# Vertex_V1.net
KiCad netlist of a schematic drawn in EAGLE
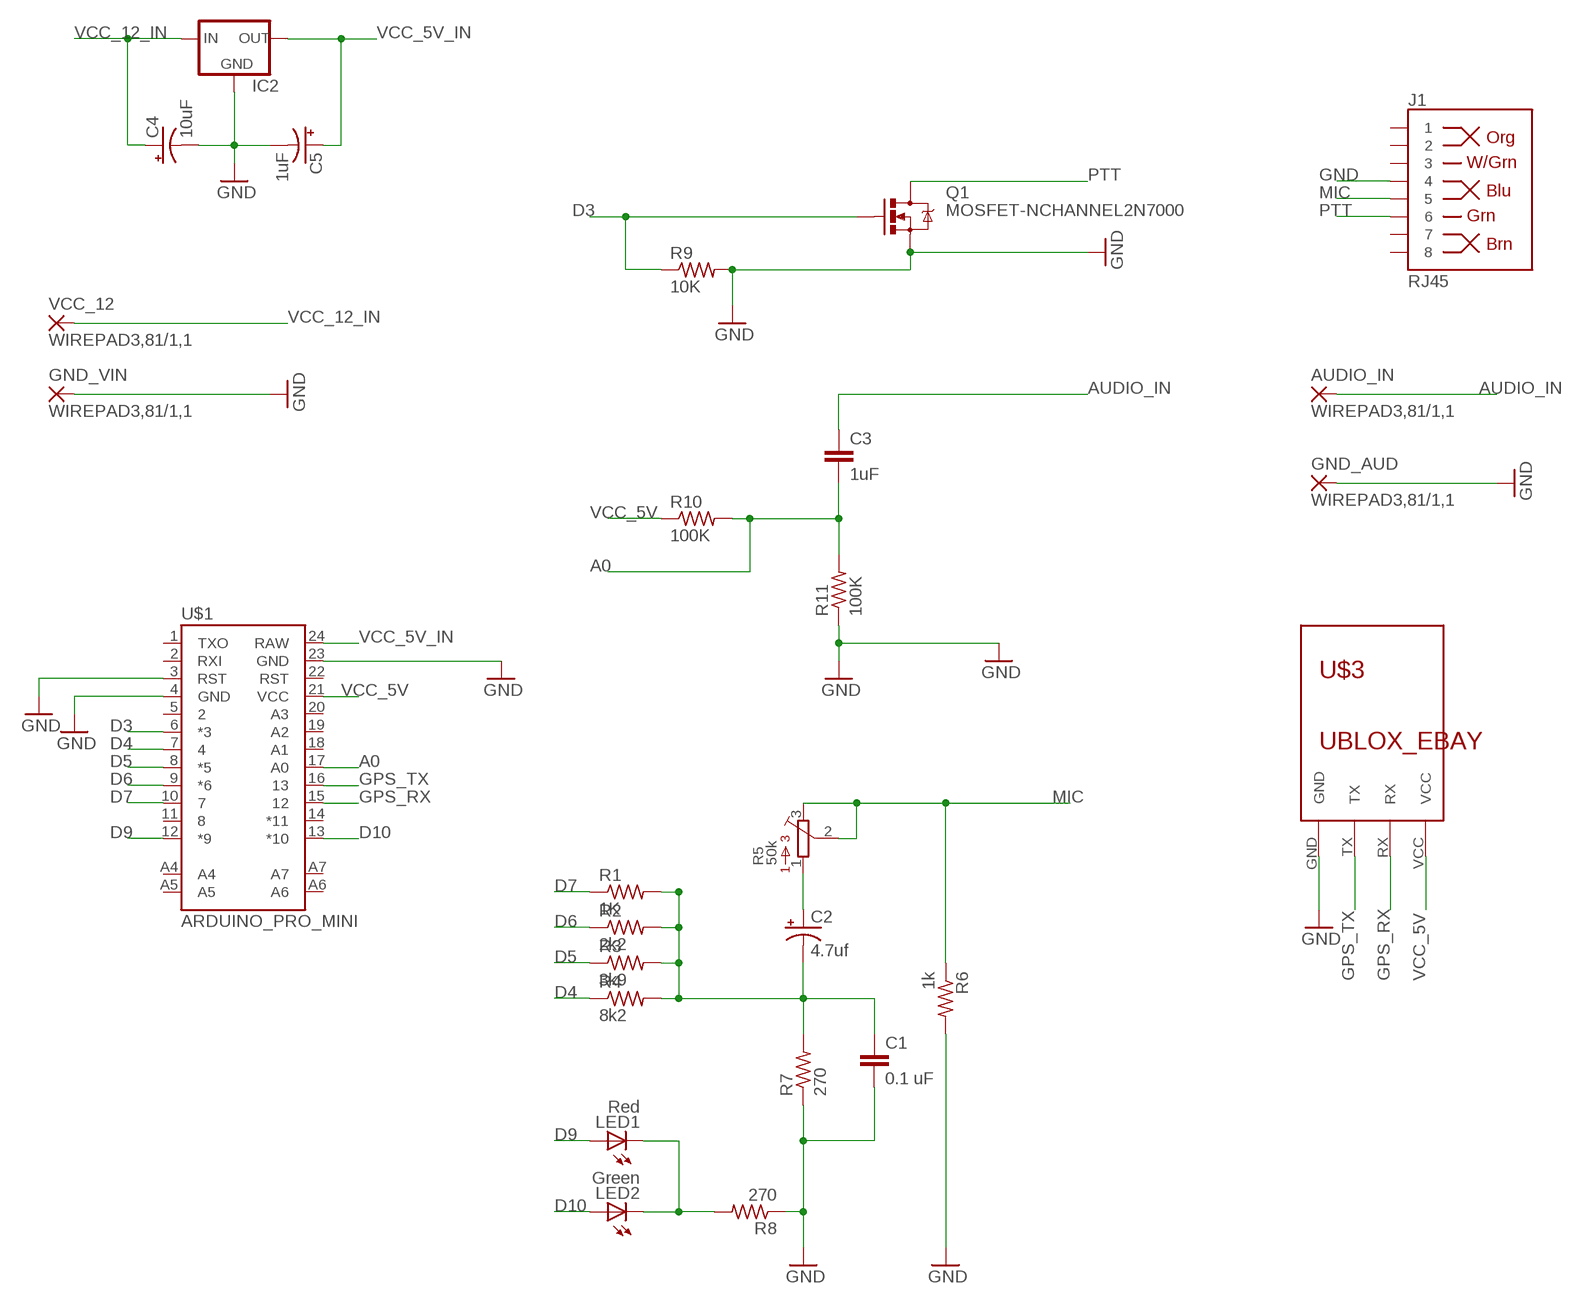
[diagram p0: schematic, sheet 1]

(export (version "E")
  (design (tool "Eeschema 10.0.6"))
  (components
    (comp (ref "AUDIO_IN")
      (value "WIREPAD3,81/1,1")
      (footprint "eagle-import:3,81_1,1")
      (libsource (lib "eagle-import") (part "WIREPAD3,81/1,1"))
    )
    (comp (ref "C1")
      (value "0.1 uF")
      (footprint "eagle-import:CAP-PTH-SMALL-KIT")
      (libsource (lib "eagle-import") (part "0.1UF-50V-20%(PTH)KIT-EZ"))
    )
    (comp (ref "C2")
      (value "4.7uf")
      (footprint "eagle-import:CPOL-RADIAL-10UF-25V")
      (libsource (lib "eagle-import") (part "CAP_POLPTH2"))
    )
    (comp (ref "C3")
      (value "1uF")
      (footprint "eagle-import:CAP-PTH-SMALL-KIT")
      (libsource (lib "eagle-import") (part "0.1UF-50V-20%(PTH)KIT-EZ"))
    )
    (comp (ref "C4")
      (value "10uF")
      (footprint "eagle-import:CPOL-RADIAL-10UF-25V")
      (libsource (lib "eagle-import") (part "CAP_POLPTH2"))
    )
    (comp (ref "C5")
      (value "1uF")
      (footprint "eagle-import:CPOL-RADIAL-10UF-25V")
      (libsource (lib "eagle-import") (part "CAP_POLPTH2"))
    )
    (comp (ref "GND_AUD")
      (value "WIREPAD3,81/1,1")
      (footprint "eagle-import:3,81_1,1")
      (libsource (lib "eagle-import") (part "WIREPAD3,81/1,1"))
    )
    (comp (ref "GND_VIN")
      (value "WIREPAD3,81/1,1")
      (footprint "eagle-import:3,81_1,1")
      (libsource (lib "eagle-import") (part "WIREPAD3,81/1,1"))
    )
    (comp (ref "IC2")
      (value "78XXS")
      (footprint "eagle-import:78XXS")
      (libsource (lib "eagle-import") (part "78XXS"))
    )
    (comp (ref "J1")
      (value "RJ45")
      (footprint "eagle-import:RJ45-8")
      (libsource (lib "eagle-import") (part "RJ45-8PTH"))
    )
    (comp (ref "LED1")
      (value "Red")
      (footprint "eagle-import:LED5MM")
      (libsource (lib "eagle-import") (part "LED5MM"))
    )
    (comp (ref "LED2")
      (value "Green")
      (footprint "eagle-import:LED5MM")
      (libsource (lib "eagle-import") (part "LED5MM"))
    )
    (comp (ref "Q1")
      (value "MOSFET-NCHANNEL2N7000")
      (footprint "eagle-import:TO-92")
      (libsource (lib "eagle-import") (part "MOSFET-NCHANNEL2N7000"))
    )
    (comp (ref "R1")
      (value "1K")
      (footprint "eagle-import:0309V")
      (libsource (lib "eagle-import") (part "R-US_0309/V"))
    )
    (comp (ref "R2")
      (value "2k2")
      (footprint "eagle-import:0309V")
      (libsource (lib "eagle-import") (part "R-US_0309/V"))
    )
    (comp (ref "R3")
      (value "3k9")
      (footprint "eagle-import:0309V")
      (libsource (lib "eagle-import") (part "R-US_0309/V"))
    )
    (comp (ref "R4")
      (value "8k2")
      (footprint "eagle-import:0309V")
      (libsource (lib "eagle-import") (part "R-US_0309/V"))
    )
    (comp (ref "R5")
      (value "50k")
      (footprint "eagle-import:3362P")
      (libsource (lib "eagle-import") (part "3362P"))
    )
    (comp (ref "R6")
      (value "1k")
      (footprint "eagle-import:0309V")
      (libsource (lib "eagle-import") (part "R-US_0309/V"))
    )
    (comp (ref "R7")
      (value "270")
      (footprint "eagle-import:0309V")
      (libsource (lib "eagle-import") (part "R-US_0309/V"))
    )
    (comp (ref "R8")
      (value "270")
      (footprint "eagle-import:0309V")
      (libsource (lib "eagle-import") (part "R-US_0309/V"))
    )
    (comp (ref "R9")
      (value "10K")
      (footprint "eagle-import:0309V")
      (libsource (lib "eagle-import") (part "R-US_0309/V"))
    )
    (comp (ref "R10")
      (value "100K")
      (footprint "eagle-import:0309V")
      (libsource (lib "eagle-import") (part "R-US_0309/V"))
    )
    (comp (ref "R11")
      (value "100K")
      (footprint "eagle-import:0309V")
      (libsource (lib "eagle-import") (part "R-US_0309/V"))
    )
    (comp (ref "U$1")
      (value "ARDUINO_PRO_MINI")
      (footprint "eagle-import:ARDUINO_PRO_MINI")
      (libsource (lib "eagle-import") (part "ARDUINO_PRO_MINI"))
    )
    (comp (ref "U$3")
      (value "UBLOX_EBAY")
      (footprint "eagle-import:UBLOX_EBAY")
      (libsource (lib "eagle-import") (part "UBLOX_EBAY"))
    )
    (comp (ref "VCC_12")
      (value "WIREPAD3,81/1,1")
      (footprint "eagle-import:3,81_1,1")
      (libsource (lib "eagle-import") (part "WIREPAD3,81/1,1"))
    )
  )
  (nets
    (net (code "1") (name "/A0") (class "Default")
      (node (ref "C3") (pin "2") (pinfunction "2_2") (pintype "passive"))
      (node (ref "R10") (pin "2") (pinfunction "2_2") (pintype "passive"))
      (node (ref "R11") (pin "2") (pinfunction "2_2") (pintype "passive"))
      (node (ref "U$1") (pin "17") (pinfunction "A0_17") (pintype "bidirectional"))
    )
    (net (code "2") (name "/AUDIO_IN") (class "Default")
      (node (ref "AUDIO_IN") (pin "1") (pinfunction "P_1") (pintype "passive"))
      (node (ref "C3") (pin "1") (pinfunction "1_1") (pintype "passive"))
    )
    (net (code "3") (name "/D3") (class "Default")
      (node (ref "Q1") (pin "2") (pinfunction "G_2") (pintype "passive"))
      (node (ref "R9") (pin "1") (pinfunction "1_1") (pintype "passive"))
      (node (ref "U$1") (pin "6") (pinfunction "*3_6") (pintype "bidirectional"))
    )
    (net (code "4") (name "/D4") (class "Default")
      (node (ref "R4") (pin "1") (pinfunction "1_1") (pintype "passive"))
      (node (ref "U$1") (pin "7") (pinfunction "4_7") (pintype "bidirectional"))
    )
    (net (code "5") (name "/D5") (class "Default")
      (node (ref "R3") (pin "1") (pinfunction "1_1") (pintype "passive"))
      (node (ref "U$1") (pin "8") (pinfunction "*5_8") (pintype "bidirectional"))
    )
    (net (code "6") (name "/D6") (class "Default")
      (node (ref "R2") (pin "1") (pinfunction "1_1") (pintype "passive"))
      (node (ref "U$1") (pin "9") (pinfunction "*6_9") (pintype "bidirectional"))
    )
    (net (code "7") (name "/D7") (class "Default")
      (node (ref "R1") (pin "1") (pinfunction "1_1") (pintype "passive"))
      (node (ref "U$1") (pin "10") (pinfunction "7_10") (pintype "bidirectional"))
    )
    (net (code "8") (name "/D9") (class "Default")
      (node (ref "LED1") (pin "A") (pinfunction "A_A") (pintype "passive"))
      (node (ref "U$1") (pin "12") (pinfunction "*9_12") (pintype "bidirectional"))
    )
    (net (code "9") (name "/D10") (class "Default")
      (node (ref "LED2") (pin "A") (pinfunction "A_A") (pintype "passive"))
      (node (ref "U$1") (pin "13") (pinfunction "*10_13") (pintype "bidirectional"))
    )
    (net (code "10") (name "/GPS_RX") (class "Default")
      (node (ref "U$1") (pin "15") (pinfunction "12_15") (pintype "bidirectional"))
      (node (ref "U$3") (pin "RX") (pinfunction "RX_RX") (pintype "bidirectional"))
    )
    (net (code "11") (name "/GPS_TX") (class "Default")
      (node (ref "U$1") (pin "16") (pinfunction "13_16") (pintype "bidirectional"))
      (node (ref "U$3") (pin "TX") (pinfunction "TX_TX") (pintype "bidirectional"))
    )
    (net (code "12") (name "/MIC") (class "Default")
      (node (ref "J1") (pin "5") (pinfunction "5_5") (pintype "bidirectional"))
      (node (ref "R5") (pin "2") (pinfunction "2_2") (pintype "passive"))
      (node (ref "R5") (pin "3") (pinfunction "3_3") (pintype "passive"))
      (node (ref "R6") (pin "1") (pinfunction "1_1") (pintype "passive"))
    )
    (net (code "13") (name "/PTT") (class "Default")
      (node (ref "J1") (pin "6") (pinfunction "6_6") (pintype "bidirectional"))
      (node (ref "Q1") (pin "3") (pinfunction "D_3") (pintype "passive"))
    )
    (net (code "14") (name "/VCC_5V") (class "Default")
      (node (ref "R10") (pin "1") (pinfunction "1_1") (pintype "passive"))
      (node (ref "U$1") (pin "21") (pinfunction "VCC_21") (pintype "bidirectional"))
      (node (ref "U$3") (pin "VCC") (pinfunction "VCC_VCC") (pintype "bidirectional"))
    )
    (net (code "15") (name "/VCC_5V_IN") (class "Default")
      (node (ref "C5") (pin "1") (pinfunction "+_1") (pintype "passive"))
      (node (ref "IC2") (pin "OUT") (pinfunction "OUT_OUT") (pintype "passive"))
      (node (ref "U$1") (pin "24") (pinfunction "RAW_24") (pintype "bidirectional"))
    )
    (net (code "16") (name "/VCC_12_IN") (class "Default")
      (node (ref "C4") (pin "1") (pinfunction "+_1") (pintype "passive"))
      (node (ref "IC2") (pin "IN") (pinfunction "IN_IN") (pintype "input"))
      (node (ref "VCC_12") (pin "1") (pinfunction "P_1") (pintype "passive"))
    )
    (net (code "17") (name "GND") (class "Default")
      (node (ref "C1") (pin "2") (pinfunction "2_2") (pintype "passive"))
      (node (ref "C4") (pin "2") (pinfunction "-_2") (pintype "passive"))
      (node (ref "C5") (pin "2") (pinfunction "-_2") (pintype "passive"))
      (node (ref "GND_AUD") (pin "1") (pinfunction "P_1") (pintype "passive"))
      (node (ref "GND_VIN") (pin "1") (pinfunction "P_1") (pintype "passive"))
      (node (ref "IC2") (pin "GND") (pinfunction "GND_GND") (pintype "input"))
      (node (ref "J1") (pin "4") (pinfunction "4_4") (pintype "bidirectional"))
      (node (ref "Q1") (pin "1") (pinfunction "S_1") (pintype "passive"))
      (node (ref "R11") (pin "1") (pinfunction "1_1") (pintype "passive"))
      (node (ref "R6") (pin "2") (pinfunction "2_2") (pintype "passive"))
      (node (ref "R7") (pin "1") (pinfunction "1_1") (pintype "passive"))
      (node (ref "R8") (pin "1") (pinfunction "1_1") (pintype "passive"))
      (node (ref "R9") (pin "2") (pinfunction "2_2") (pintype "passive"))
      (node (ref "U$1") (pin "23") (pinfunction "GND_23") (pintype "bidirectional"))
      (node (ref "U$1") (pin "3") (pinfunction "RST_3") (pintype "bidirectional"))
      (node (ref "U$1") (pin "4") (pinfunction "GND_4") (pintype "bidirectional"))
      (node (ref "U$3") (pin "GND") (pinfunction "GND_GND") (pintype "bidirectional"))
    )
    (net (code "18") (name "Net-(C2-+)") (class "Default")
      (node (ref "C2") (pin "1") (pinfunction "+_1") (pintype "passive"))
      (node (ref "R5") (pin "1") (pinfunction "1_1") (pintype "passive"))
    )
    (net (code "19") (name "Net-(C2--)") (class "Default")
      (node (ref "C1") (pin "1") (pinfunction "1_1") (pintype "passive"))
      (node (ref "C2") (pin "2") (pinfunction "-_2") (pintype "passive"))
      (node (ref "R1") (pin "2") (pinfunction "2_2") (pintype "passive"))
      (node (ref "R2") (pin "2") (pinfunction "2_2") (pintype "passive"))
      (node (ref "R3") (pin "2") (pinfunction "2_2") (pintype "passive"))
      (node (ref "R4") (pin "2") (pinfunction "2_2") (pintype "passive"))
      (node (ref "R7") (pin "2") (pinfunction "2_2") (pintype "passive"))
    )
    (net (code "20") (name "Net-(LED1-C)") (class "Default")
      (node (ref "LED1") (pin "K") (pinfunction "C_K") (pintype "passive"))
      (node (ref "LED2") (pin "K") (pinfunction "C_K") (pintype "passive"))
      (node (ref "R8") (pin "2") (pinfunction "2_2") (pintype "passive"))
    )
    (net (code "21") (name "unconnected-(J1-Pad1)") (class "Default")
      (node (ref "J1") (pin "1") (pinfunction "1_1") (pintype "bidirectional"))
    )
    (net (code "22") (name "unconnected-(J1-Pad2)") (class "Default")
      (node (ref "J1") (pin "2") (pinfunction "2_2") (pintype "bidirectional"))
    )
    (net (code "23") (name "unconnected-(J1-Pad3)") (class "Default")
      (node (ref "J1") (pin "3") (pinfunction "3_3") (pintype "bidirectional"))
    )
    (net (code "24") (name "unconnected-(J1-Pad7)") (class "Default")
      (node (ref "J1") (pin "7") (pinfunction "7_7") (pintype "bidirectional"))
    )
    (net (code "25") (name "unconnected-(J1-Pad8)") (class "Default")
      (node (ref "J1") (pin "8") (pinfunction "8_8") (pintype "bidirectional"))
    )
    (net (code "26") (name "unconnected-(U$1-*11-Pad14)") (class "Default")
      (node (ref "U$1") (pin "14") (pinfunction "*11_14") (pintype "bidirectional"))
    )
    (net (code "27") (name "unconnected-(U$1-2-Pad5)") (class "Default")
      (node (ref "U$1") (pin "5") (pinfunction "2_5") (pintype "bidirectional"))
    )
    (net (code "28") (name "unconnected-(U$1-8-Pad11)") (class "Default")
      (node (ref "U$1") (pin "11") (pinfunction "8_11") (pintype "bidirectional"))
    )
    (net (code "29") (name "unconnected-(U$1-A1-Pad18)") (class "Default")
      (node (ref "U$1") (pin "18") (pinfunction "A1_18") (pintype "bidirectional"))
    )
    (net (code "30") (name "unconnected-(U$1-A2-Pad19)") (class "Default")
      (node (ref "U$1") (pin "19") (pinfunction "A2_19") (pintype "bidirectional"))
    )
    (net (code "31") (name "unconnected-(U$1-A3-Pad20)") (class "Default")
      (node (ref "U$1") (pin "20") (pinfunction "A3_20") (pintype "bidirectional"))
    )
    (net (code "32") (name "unconnected-(U$1-PadA4)") (class "Default")
      (node (ref "U$1") (pin "A4") (pinfunction "A4_A4") (pintype "bidirectional"))
    )
    (net (code "33") (name "unconnected-(U$1-PadA5)") (class "Default")
      (node (ref "U$1") (pin "A5") (pinfunction "A5_A5") (pintype "bidirectional"))
    )
    (net (code "34") (name "unconnected-(U$1-PadA6)") (class "Default")
      (node (ref "U$1") (pin "A6") (pinfunction "A6_A6") (pintype "bidirectional"))
    )
    (net (code "35") (name "unconnected-(U$1-PadA7)") (class "Default")
      (node (ref "U$1") (pin "A7") (pinfunction "A7_A7") (pintype "bidirectional"))
    )
    (net (code "36") (name "unconnected-(U$1-RST-Pad22)") (class "Default")
      (node (ref "U$1") (pin "22") (pinfunction "RST_22") (pintype "bidirectional"))
    )
    (net (code "37") (name "unconnected-(U$1-RXI-Pad2)") (class "Default")
      (node (ref "U$1") (pin "2") (pinfunction "RXI_2") (pintype "bidirectional"))
    )
    (net (code "38") (name "unconnected-(U$1-TXO-Pad1)") (class "Default")
      (node (ref "U$1") (pin "1") (pinfunction "TXO_1") (pintype "bidirectional"))
    )
  )
)
